# Open-GCI.net
KiCad netlist of a schematic drawn in EAGLE
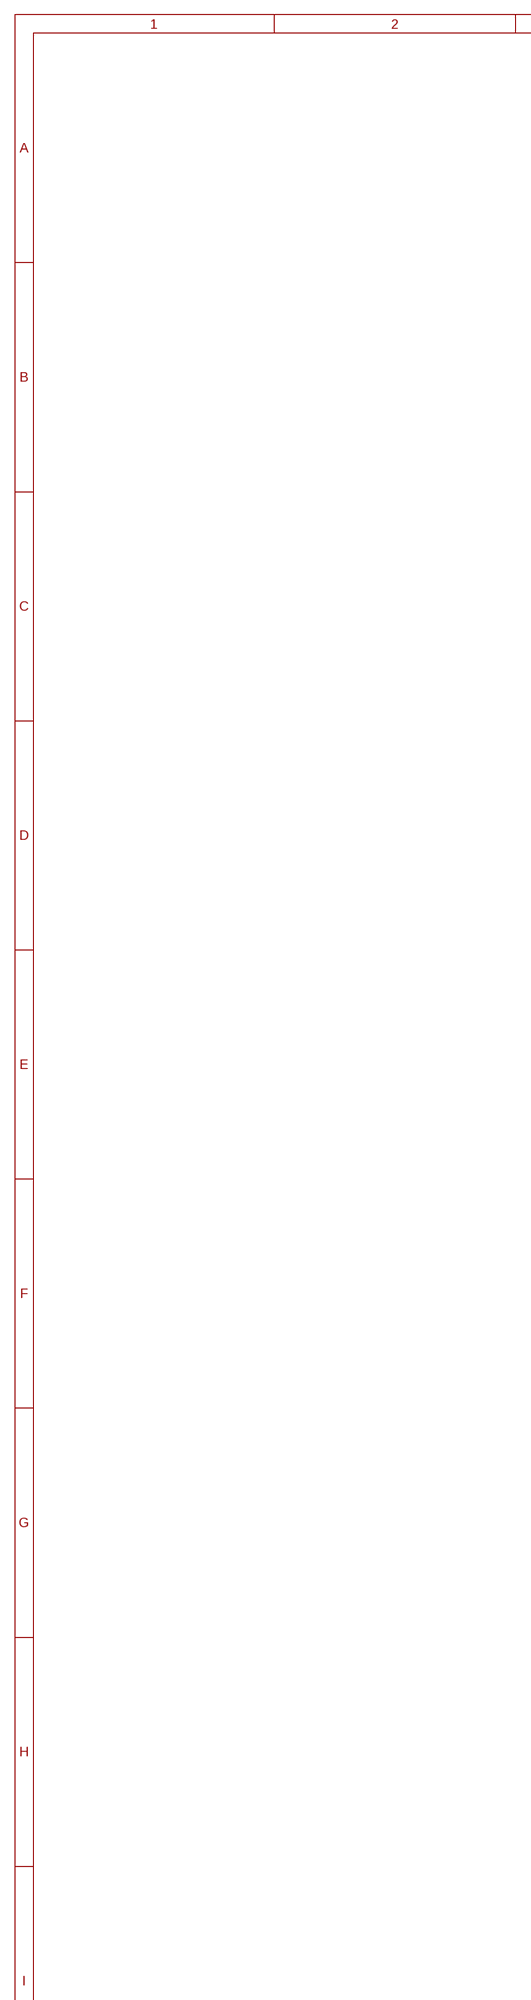
[diagram p0: schematic, sheet 1, part 1 of 2]
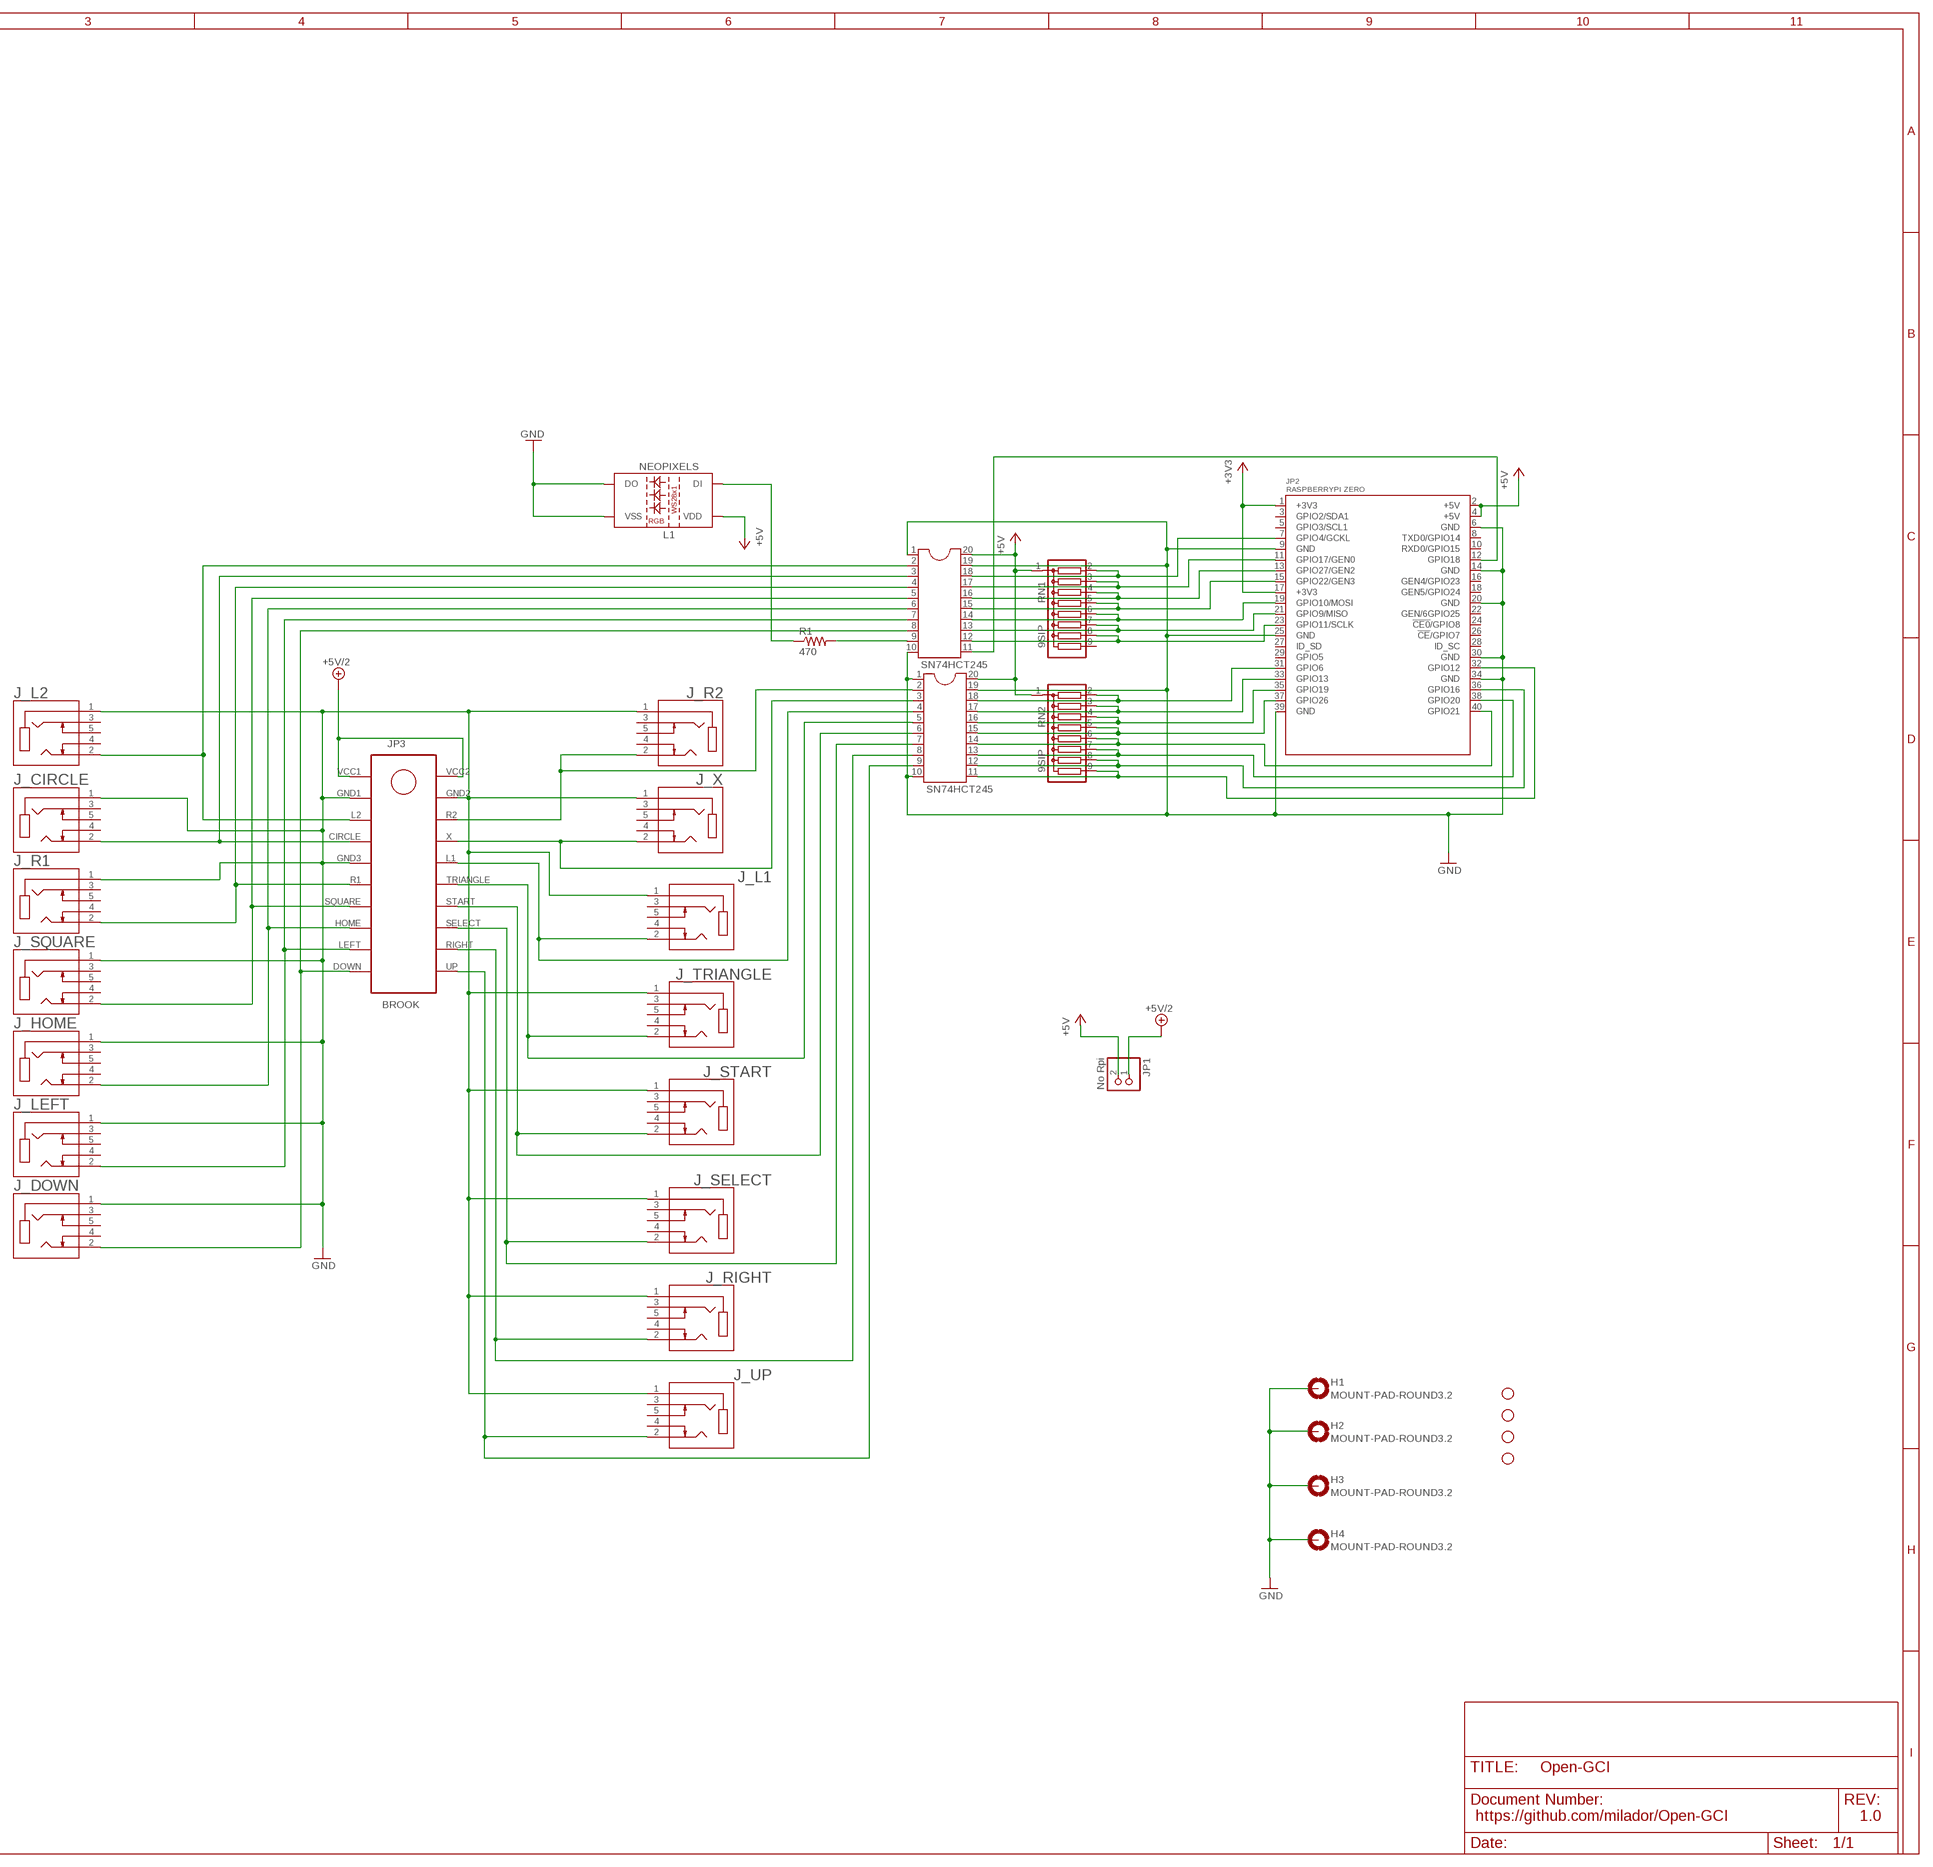
[diagram p1: schematic, sheet 1, part 2 of 2]

(export (version "E")
  (design (tool "Eeschema 10.0.6"))
  (components
    (comp (ref "H1")
      (value "MOUNT-PAD-ROUND3.2")
      (footprint "eagle-import:3,2-PAD")
      (libsource (lib "eagle-import") (part "MOUNT-PAD-ROUND3.2"))
    )
    (comp (ref "H2")
      (value "MOUNT-PAD-ROUND3.2")
      (footprint "eagle-import:3,2-PAD")
      (libsource (lib "eagle-import") (part "MOUNT-PAD-ROUND3.2"))
    )
    (comp (ref "H3")
      (value "MOUNT-PAD-ROUND3.2")
      (footprint "eagle-import:3,2-PAD")
      (libsource (lib "eagle-import") (part "MOUNT-PAD-ROUND3.2"))
    )
    (comp (ref "H4")
      (value "MOUNT-PAD-ROUND3.2")
      (footprint "eagle-import:3,2-PAD")
      (libsource (lib "eagle-import") (part "MOUNT-PAD-ROUND3.2"))
    )
    (comp (ref "H5")
      (value "STAND-OFF")
      (footprint "eagle-import:STAND-OFF")
      (libsource (lib "eagle-import") (part "STAND-OFF"))
    )
    (comp (ref "H6")
      (value "STAND-OFF")
      (footprint "eagle-import:STAND-OFF")
      (libsource (lib "eagle-import") (part "STAND-OFF"))
    )
    (comp (ref "H7")
      (value "STAND-OFF")
      (footprint "eagle-import:STAND-OFF")
      (libsource (lib "eagle-import") (part "STAND-OFF"))
    )
    (comp (ref "H8")
      (value "STAND-OFF")
      (footprint "eagle-import:STAND-OFF")
      (libsource (lib "eagle-import") (part "STAND-OFF"))
    )
    (comp (ref "IC1")
      (value "SN74HCT245")
      (footprint "eagle-import:SN74HCT245")
      (libsource (lib "eagle-import") (part "74HCT245N"))
    )
    (comp (ref "IC2")
      (value "SN74HCT245")
      (footprint "eagle-import:SN74HCT245")
      (libsource (lib "eagle-import") (part "74HCT245N"))
    )
    (comp (ref "JP1")
      (value "No Rpi")
      (footprint "eagle-import:1X02")
      (libsource (lib "eagle-import") (part "PINHD-1X2"))
    )
    (comp (ref "JP2")
      (value "RASPBERRYPI ZERO")
      (footprint "eagle-import:RASPBERRYPI_ZERO")
      (libsource (lib "eagle-import") (part "RASPBERRYPI_ZERO"))
    )
    (comp (ref "JP3")
      (value "BROOK")
      (footprint "eagle-import:CONN_2X10")
      (libsource (lib "eagle-import") (part "BROOK_2X10_FEMALE"))
    )
    (comp (ref "J_CIRCLE")
      (value "SJ1-3535NG")
      (footprint "eagle-import:CUI_SJ1-3535NG")
      (fields (field (name "MANUFACTURER") "CUI"))
      (libsource (lib "eagle-import") (part "SJ1-3535NG"))
    )
    (comp (ref "J_DOWN")
      (value "SJ1-3535NG")
      (footprint "eagle-import:CUI_SJ1-3535NG")
      (fields (field (name "MANUFACTURER") "CUI"))
      (libsource (lib "eagle-import") (part "SJ1-3535NG"))
    )
    (comp (ref "J_HOME")
      (value "SJ1-3535NG")
      (footprint "eagle-import:CUI_SJ1-3535NG")
      (fields (field (name "MANUFACTURER") "CUI"))
      (libsource (lib "eagle-import") (part "SJ1-3535NG"))
    )
    (comp (ref "J_L1")
      (value "SJ1-3535NG")
      (footprint "eagle-import:CUI_SJ1-3535NG")
      (fields (field (name "MANUFACTURER") "CUI"))
      (libsource (lib "eagle-import") (part "SJ1-3535NG"))
    )
    (comp (ref "J_L2")
      (value "SJ1-3535NG")
      (footprint "eagle-import:CUI_SJ1-3535NG")
      (fields (field (name "MANUFACTURER") "CUI"))
      (libsource (lib "eagle-import") (part "SJ1-3535NG"))
    )
    (comp (ref "J_LEFT")
      (value "SJ1-3535NG")
      (footprint "eagle-import:CUI_SJ1-3535NG")
      (fields (field (name "MANUFACTURER") "CUI"))
      (libsource (lib "eagle-import") (part "SJ1-3535NG"))
    )
    (comp (ref "J_R1")
      (value "SJ1-3535NG")
      (footprint "eagle-import:CUI_SJ1-3535NG")
      (fields (field (name "MANUFACTURER") "CUI"))
      (libsource (lib "eagle-import") (part "SJ1-3535NG"))
    )
    (comp (ref "J_R2")
      (value "SJ1-3535NG")
      (footprint "eagle-import:CUI_SJ1-3535NG")
      (fields (field (name "MANUFACTURER") "CUI"))
      (libsource (lib "eagle-import") (part "SJ1-3535NG"))
    )
    (comp (ref "J_RIGHT")
      (value "SJ1-3535NG")
      (footprint "eagle-import:CUI_SJ1-3535NG")
      (fields (field (name "MANUFACTURER") "CUI"))
      (libsource (lib "eagle-import") (part "SJ1-3535NG"))
    )
    (comp (ref "J_SELECT")
      (value "SJ1-3535NG")
      (footprint "eagle-import:CUI_SJ1-3535NG")
      (fields (field (name "MANUFACTURER") "CUI"))
      (libsource (lib "eagle-import") (part "SJ1-3535NG"))
    )
    (comp (ref "J_SQUARE")
      (value "SJ1-3535NG")
      (footprint "eagle-import:CUI_SJ1-3535NG")
      (fields (field (name "MANUFACTURER") "CUI"))
      (libsource (lib "eagle-import") (part "SJ1-3535NG"))
    )
    (comp (ref "J_START")
      (value "SJ1-3535NG")
      (footprint "eagle-import:CUI_SJ1-3535NG")
      (fields (field (name "MANUFACTURER") "CUI"))
      (libsource (lib "eagle-import") (part "SJ1-3535NG"))
    )
    (comp (ref "J_TRIANGLE")
      (value "SJ1-3535NG")
      (footprint "eagle-import:CUI_SJ1-3535NG")
      (fields (field (name "MANUFACTURER") "CUI"))
      (libsource (lib "eagle-import") (part "SJ1-3535NG"))
    )
    (comp (ref "J_UP")
      (value "SJ1-3535NG")
      (footprint "eagle-import:CUI_SJ1-3535NG")
      (fields (field (name "MANUFACTURER") "CUI"))
      (libsource (lib "eagle-import") (part "SJ1-3535NG"))
    )
    (comp (ref "J_X")
      (value "SJ1-3535NG")
      (footprint "eagle-import:CUI_SJ1-3535NG")
      (fields (field (name "MANUFACTURER") "CUI"))
      (libsource (lib "eagle-import") (part "SJ1-3535NG"))
    )
    (comp (ref "L1")
      (value "NEOPIXELS")
      (footprint "eagle-import:NEOPIXELS-5MM")
      (libsource (lib "eagle-import") (part "NEOPIXELS-5MM"))
    )
    (comp (ref "R1")
      (value "470")
      (footprint "eagle-import:0204_7")
      (libsource (lib "eagle-import") (part "R-US_0204/7"))
    )
    (comp (ref "RN1")
      (value "9SIP")
      (footprint "eagle-import:SIL9")
      (libsource (lib "eagle-import") (part "SIL9"))
    )
    (comp (ref "RN2")
      (value "9SIP")
      (footprint "eagle-import:SIL9")
      (libsource (lib "eagle-import") (part "SIL9"))
    )
  )
  (nets
    (net (code "1") (name "+3V3") (class "Default")
      (node (ref "JP2") (pin "1") (pinfunction "+3V3_1") (pintype "power_in"))
      (node (ref "JP2") (pin "17") (pinfunction "+3V3_17") (pintype "power_in"))
    )
    (net (code "2") (name "+5V") (class "Default")
      (node (ref "IC1") (pin "20") (pinfunction "20_20") (pintype "passive"))
      (node (ref "IC2") (pin "20") (pinfunction "20_20") (pintype "passive"))
      (node (ref "JP1") (pin "2") (pinfunction "2_2") (pintype "passive"))
      (node (ref "JP2") (pin "2") (pinfunction "+5V_2") (pintype "power_in"))
      (node (ref "JP2") (pin "4") (pinfunction "+5V_4") (pintype "power_in"))
      (node (ref "L1") (pin "2") (pinfunction "VDD_2") (pintype "bidirectional"))
      (node (ref "RN1") (pin "1") (pinfunction "1_1") (pintype "passive"))
      (node (ref "RN2") (pin "1") (pinfunction "1_1") (pintype "passive"))
    )
    (net (code "3") (name "+5V{slash}2") (class "Default")
      (node (ref "JP1") (pin "1") (pinfunction "1_1") (pintype "passive"))
      (node (ref "JP3") (pin "VCC1") (pinfunction "VCC1_VCC1") (pintype "passive"))
      (node (ref "JP3") (pin "VCC2") (pinfunction "VCC2_VCC2") (pintype "passive"))
    )
    (net (code "4") (name "GND") (class "Default")
      (node (ref "H1") (pin "B3,2") (pinfunction "MOUNT_B3,2") (pintype "passive"))
      (node (ref "H2") (pin "B3,2") (pinfunction "MOUNT_B3,2") (pintype "passive"))
      (node (ref "H3") (pin "B3,2") (pinfunction "MOUNT_B3,2") (pintype "passive"))
      (node (ref "H4") (pin "B3,2") (pinfunction "MOUNT_B3,2") (pintype "passive"))
      (node (ref "IC1") (pin "1") (pinfunction "1_1") (pintype "passive"))
      (node (ref "IC1") (pin "10") (pinfunction "10_10") (pintype "passive"))
      (node (ref "IC1") (pin "19") (pinfunction "19_19") (pintype "passive"))
      (node (ref "IC2") (pin "1") (pinfunction "1_1") (pintype "passive"))
      (node (ref "IC2") (pin "10") (pinfunction "10_10") (pintype "passive"))
      (node (ref "IC2") (pin "19") (pinfunction "19_19") (pintype "passive"))
      (node (ref "JP2") (pin "14") (pinfunction "GND_14") (pintype "power_in"))
      (node (ref "JP2") (pin "20") (pinfunction "GND_20") (pintype "power_in"))
      (node (ref "JP2") (pin "25") (pinfunction "GND_25") (pintype "power_in"))
      (node (ref "JP2") (pin "30") (pinfunction "GND_30") (pintype "power_in"))
      (node (ref "JP2") (pin "34") (pinfunction "GND_34") (pintype "power_in"))
      (node (ref "JP2") (pin "39") (pinfunction "GND_39") (pintype "power_in"))
      (node (ref "JP2") (pin "6") (pinfunction "GND_6") (pintype "power_in"))
      (node (ref "JP2") (pin "9") (pinfunction "GND_9") (pintype "power_in"))
      (node (ref "JP3") (pin "GND1") (pinfunction "GND1_GND1") (pintype "passive"))
      (node (ref "JP3") (pin "GND2") (pinfunction "GND2_GND2") (pintype "passive"))
      (node (ref "JP3") (pin "GND3") (pinfunction "GND3_GND3") (pintype "passive"))
      (node (ref "J_CIRCLE") (pin "1") (pinfunction "1_1") (pintype "passive"))
      (node (ref "J_DOWN") (pin "1") (pinfunction "1_1") (pintype "passive"))
      (node (ref "J_HOME") (pin "1") (pinfunction "1_1") (pintype "passive"))
      (node (ref "J_L1") (pin "1") (pinfunction "1_1") (pintype "passive"))
      (node (ref "J_L2") (pin "1") (pinfunction "1_1") (pintype "passive"))
      (node (ref "J_LEFT") (pin "1") (pinfunction "1_1") (pintype "passive"))
      (node (ref "J_R1") (pin "1") (pinfunction "1_1") (pintype "passive"))
      (node (ref "J_R2") (pin "1") (pinfunction "1_1") (pintype "passive"))
      (node (ref "J_RIGHT") (pin "1") (pinfunction "1_1") (pintype "passive"))
      (node (ref "J_SELECT") (pin "1") (pinfunction "1_1") (pintype "passive"))
      (node (ref "J_SQUARE") (pin "1") (pinfunction "1_1") (pintype "passive"))
      (node (ref "J_START") (pin "1") (pinfunction "1_1") (pintype "passive"))
      (node (ref "J_TRIANGLE") (pin "1") (pinfunction "1_1") (pintype "passive"))
      (node (ref "J_UP") (pin "1") (pinfunction "1_1") (pintype "passive"))
      (node (ref "J_X") (pin "1") (pinfunction "1_1") (pintype "passive"))
      (node (ref "L1") (pin "3") (pinfunction "VSS_3") (pintype "bidirectional"))
      (node (ref "L1") (pin "4") (pinfunction "DO_4") (pintype "bidirectional"))
    )
    (net (code "5") (name "Net-(IC1-Pad2)") (class "Default")
      (node (ref "IC1") (pin "2") (pinfunction "2_2") (pintype "passive"))
      (node (ref "JP3") (pin "L2") (pinfunction "L2_L2") (pintype "passive"))
      (node (ref "J_L2") (pin "2") (pinfunction "2_2") (pintype "passive"))
    )
    (net (code "6") (name "Net-(IC1-Pad3)") (class "Default")
      (node (ref "IC1") (pin "3") (pinfunction "3_3") (pintype "passive"))
      (node (ref "JP3") (pin "CIRCLE") (pinfunction "CIRCLE_CIRCLE") (pintype "passive"))
      (node (ref "J_CIRCLE") (pin "2") (pinfunction "2_2") (pintype "passive"))
    )
    (net (code "7") (name "Net-(IC1-Pad4)") (class "Default")
      (node (ref "IC1") (pin "4") (pinfunction "4_4") (pintype "passive"))
      (node (ref "JP3") (pin "R1") (pinfunction "R1_R1") (pintype "passive"))
      (node (ref "J_R1") (pin "2") (pinfunction "2_2") (pintype "passive"))
    )
    (net (code "8") (name "Net-(IC1-Pad5)") (class "Default")
      (node (ref "IC1") (pin "5") (pinfunction "5_5") (pintype "passive"))
      (node (ref "JP3") (pin "SQUARE") (pinfunction "SQUARE_SQUARE") (pintype "passive"))
      (node (ref "J_SQUARE") (pin "2") (pinfunction "2_2") (pintype "passive"))
    )
    (net (code "9") (name "Net-(IC1-Pad6)") (class "Default")
      (node (ref "IC1") (pin "6") (pinfunction "6_6") (pintype "passive"))
      (node (ref "JP3") (pin "HOME") (pinfunction "HOME_HOME") (pintype "passive"))
      (node (ref "J_HOME") (pin "2") (pinfunction "2_2") (pintype "passive"))
    )
    (net (code "10") (name "Net-(IC1-Pad7)") (class "Default")
      (node (ref "IC1") (pin "7") (pinfunction "7_7") (pintype "passive"))
      (node (ref "JP3") (pin "LEFT") (pinfunction "LEFT_LEFT") (pintype "passive"))
      (node (ref "J_LEFT") (pin "2") (pinfunction "2_2") (pintype "passive"))
    )
    (net (code "11") (name "Net-(IC1-Pad8)") (class "Default")
      (node (ref "IC1") (pin "8") (pinfunction "8_8") (pintype "passive"))
      (node (ref "JP3") (pin "DOWN") (pinfunction "DOWN_DOWN") (pintype "passive"))
      (node (ref "J_DOWN") (pin "2") (pinfunction "2_2") (pintype "passive"))
    )
    (net (code "12") (name "Net-(IC1-Pad9)") (class "Default")
      (node (ref "IC1") (pin "9") (pinfunction "9_9") (pintype "passive"))
      (node (ref "R1") (pin "2") (pinfunction "2_2") (pintype "passive"))
    )
    (net (code "13") (name "Net-(IC2-Pad2)") (class "Default")
      (node (ref "IC2") (pin "2") (pinfunction "2_2") (pintype "passive"))
      (node (ref "JP3") (pin "R2") (pinfunction "R2_R2") (pintype "passive"))
      (node (ref "J_R2") (pin "2") (pinfunction "2_2") (pintype "passive"))
    )
    (net (code "14") (name "Net-(IC2-Pad3)") (class "Default")
      (node (ref "IC2") (pin "3") (pinfunction "3_3") (pintype "passive"))
      (node (ref "JP3") (pin "X") (pinfunction "X_X") (pintype "passive"))
      (node (ref "J_X") (pin "2") (pinfunction "2_2") (pintype "passive"))
    )
    (net (code "15") (name "Net-(IC2-Pad4)") (class "Default")
      (node (ref "IC2") (pin "4") (pinfunction "4_4") (pintype "passive"))
      (node (ref "JP3") (pin "L1") (pinfunction "L1_L1") (pintype "passive"))
      (node (ref "J_L1") (pin "2") (pinfunction "2_2") (pintype "passive"))
    )
    (net (code "16") (name "Net-(IC2-Pad5)") (class "Default")
      (node (ref "IC2") (pin "5") (pinfunction "5_5") (pintype "passive"))
      (node (ref "JP3") (pin "TRIANGLE") (pinfunction "TRIANGLE_TRIANGLE") (pintype "passive"))
      (node (ref "J_TRIANGLE") (pin "2") (pinfunction "2_2") (pintype "passive"))
    )
    (net (code "17") (name "Net-(IC2-Pad6)") (class "Default")
      (node (ref "IC2") (pin "6") (pinfunction "6_6") (pintype "passive"))
      (node (ref "JP3") (pin "START") (pinfunction "START_START") (pintype "passive"))
      (node (ref "J_START") (pin "2") (pinfunction "2_2") (pintype "passive"))
    )
    (net (code "18") (name "Net-(IC2-Pad7)") (class "Default")
      (node (ref "IC2") (pin "7") (pinfunction "7_7") (pintype "passive"))
      (node (ref "JP3") (pin "SELECT") (pinfunction "SELECT_SELECT") (pintype "passive"))
      (node (ref "J_SELECT") (pin "2") (pinfunction "2_2") (pintype "passive"))
    )
    (net (code "19") (name "Net-(IC2-Pad8)") (class "Default")
      (node (ref "IC2") (pin "8") (pinfunction "8_8") (pintype "passive"))
      (node (ref "JP3") (pin "RIGHT") (pinfunction "RIGHT_RIGHT") (pintype "passive"))
      (node (ref "J_RIGHT") (pin "2") (pinfunction "2_2") (pintype "passive"))
    )
    (net (code "20") (name "Net-(IC2-Pad9)") (class "Default")
      (node (ref "IC2") (pin "9") (pinfunction "9_9") (pintype "passive"))
      (node (ref "JP3") (pin "UP") (pinfunction "UP_UP") (pintype "passive"))
      (node (ref "J_UP") (pin "2") (pinfunction "2_2") (pintype "passive"))
    )
    (net (code "21") (name "Net-(JP2-GPIO4{slash}GCKL)") (class "Default")
      (node (ref "IC1") (pin "18") (pinfunction "18_18") (pintype "passive"))
      (node (ref "JP2") (pin "7") (pinfunction "GPIO4/GCKL_7") (pintype "bidirectional"))
      (node (ref "RN1") (pin "2") (pinfunction "2_2") (pintype "passive"))
    )
    (net (code "22") (name "Net-(JP2-GPIO6)") (class "Default")
      (node (ref "IC2") (pin "18") (pinfunction "18_18") (pintype "passive"))
      (node (ref "JP2") (pin "31") (pinfunction "GPIO6_31") (pintype "bidirectional"))
      (node (ref "RN2") (pin "2") (pinfunction "2_2") (pintype "passive"))
    )
    (net (code "23") (name "Net-(JP2-GPIO9{slash}MISO)") (class "Default")
      (node (ref "IC1") (pin "13") (pinfunction "13_13") (pintype "passive"))
      (node (ref "JP2") (pin "21") (pinfunction "GPIO9/MISO_21") (pintype "bidirectional"))
      (node (ref "RN1") (pin "7") (pinfunction "7_7") (pintype "passive"))
    )
    (net (code "24") (name "Net-(JP2-GPIO10{slash}MOSI)") (class "Default")
      (node (ref "IC1") (pin "14") (pinfunction "14_14") (pintype "passive"))
      (node (ref "JP2") (pin "19") (pinfunction "GPIO10/MOSI_19") (pintype "bidirectional"))
      (node (ref "RN1") (pin "6") (pinfunction "6_6") (pintype "passive"))
    )
    (net (code "25") (name "Net-(JP2-GPIO11{slash}SCLK)") (class "Default")
      (node (ref "IC1") (pin "12") (pinfunction "12_12") (pintype "passive"))
      (node (ref "JP2") (pin "23") (pinfunction "GPIO11/SCLK_23") (pintype "bidirectional"))
      (node (ref "RN1") (pin "8") (pinfunction "8_8") (pintype "passive"))
    )
    (net (code "26") (name "Net-(JP2-GPIO12)") (class "Default")
      (node (ref "IC2") (pin "11") (pinfunction "11_11") (pintype "passive"))
      (node (ref "JP2") (pin "32") (pinfunction "GPIO12_32") (pintype "bidirectional"))
      (node (ref "RN2") (pin "9") (pinfunction "9_9") (pintype "passive"))
    )
    (net (code "27") (name "Net-(JP2-GPIO13)") (class "Default")
      (node (ref "IC2") (pin "17") (pinfunction "17_17") (pintype "passive"))
      (node (ref "JP2") (pin "33") (pinfunction "GPIO13_33") (pintype "bidirectional"))
      (node (ref "RN2") (pin "3") (pinfunction "3_3") (pintype "passive"))
    )
    (net (code "28") (name "Net-(JP2-GPIO16)") (class "Default")
      (node (ref "IC2") (pin "12") (pinfunction "12_12") (pintype "passive"))
      (node (ref "JP2") (pin "36") (pinfunction "GPIO16_36") (pintype "bidirectional"))
      (node (ref "RN2") (pin "8") (pinfunction "8_8") (pintype "passive"))
    )
    (net (code "29") (name "Net-(JP2-GPIO17{slash}GEN0)") (class "Default")
      (node (ref "IC1") (pin "17") (pinfunction "17_17") (pintype "passive"))
      (node (ref "JP2") (pin "11") (pinfunction "GPIO17/GEN0_11") (pintype "bidirectional"))
      (node (ref "RN1") (pin "3") (pinfunction "3_3") (pintype "passive"))
    )
    (net (code "30") (name "Net-(JP2-GPIO18)") (class "Default")
      (node (ref "IC1") (pin "11") (pinfunction "11_11") (pintype "passive"))
      (node (ref "JP2") (pin "12") (pinfunction "GPIO18_12") (pintype "bidirectional"))
    )
    (net (code "31") (name "Net-(JP2-GPIO19)") (class "Default")
      (node (ref "IC2") (pin "16") (pinfunction "16_16") (pintype "passive"))
      (node (ref "JP2") (pin "35") (pinfunction "GPIO19_35") (pintype "bidirectional"))
      (node (ref "RN2") (pin "4") (pinfunction "4_4") (pintype "passive"))
    )
    (net (code "32") (name "Net-(JP2-GPIO20)") (class "Default")
      (node (ref "IC2") (pin "13") (pinfunction "13_13") (pintype "passive"))
      (node (ref "JP2") (pin "38") (pinfunction "GPIO20_38") (pintype "bidirectional"))
      (node (ref "RN2") (pin "7") (pinfunction "7_7") (pintype "passive"))
    )
    (net (code "33") (name "Net-(JP2-GPIO21)") (class "Default")
      (node (ref "IC2") (pin "14") (pinfunction "14_14") (pintype "passive"))
      (node (ref "JP2") (pin "40") (pinfunction "GPIO21_40") (pintype "bidirectional"))
      (node (ref "RN2") (pin "6") (pinfunction "6_6") (pintype "passive"))
    )
    (net (code "34") (name "Net-(JP2-GPIO22{slash}GEN3)") (class "Default")
      (node (ref "IC1") (pin "15") (pinfunction "15_15") (pintype "passive"))
      (node (ref "JP2") (pin "15") (pinfunction "GPIO22/GEN3_15") (pintype "bidirectional"))
      (node (ref "RN1") (pin "5") (pinfunction "5_5") (pintype "passive"))
    )
    (net (code "35") (name "Net-(JP2-GPIO26)") (class "Default")
      (node (ref "IC2") (pin "15") (pinfunction "15_15") (pintype "passive"))
      (node (ref "JP2") (pin "37") (pinfunction "GPIO26_37") (pintype "bidirectional"))
      (node (ref "RN2") (pin "5") (pinfunction "5_5") (pintype "passive"))
    )
    (net (code "36") (name "Net-(JP2-GPIO27{slash}GEN2)") (class "Default")
      (node (ref "IC1") (pin "16") (pinfunction "16_16") (pintype "passive"))
      (node (ref "JP2") (pin "13") (pinfunction "GPIO27/GEN2_13") (pintype "bidirectional"))
      (node (ref "RN1") (pin "4") (pinfunction "4_4") (pintype "passive"))
    )
    (net (code "37") (name "Net-(L1-DI)") (class "Default")
      (node (ref "L1") (pin "1") (pinfunction "DI_1") (pintype "bidirectional"))
      (node (ref "R1") (pin "1") (pinfunction "1_1") (pintype "passive"))
    )
    (net (code "38") (name "unconnected-(JP2-GEN4{slash}GPIO23-Pad16)") (class "Default")
      (node (ref "JP2") (pin "16") (pinfunction "GEN4/GPIO23_16") (pintype "bidirectional"))
    )
    (net (code "39") (name "unconnected-(JP2-GEN5{slash}GPIO24-Pad18)") (class "Default")
      (node (ref "JP2") (pin "18") (pinfunction "GEN5/GPIO24_18") (pintype "bidirectional"))
    )
    (net (code "40") (name "unconnected-(JP2-GEN{slash}6GPIO25-Pad22)") (class "Default")
      (node (ref "JP2") (pin "22") (pinfunction "GEN/6GPIO25_22") (pintype "bidirectional"))
    )
    (net (code "41") (name "unconnected-(JP2-GPIO2{slash}SDA1-Pad3)") (class "Default")
      (node (ref "JP2") (pin "3") (pinfunction "GPIO2/SDA1_3") (pintype "bidirectional"))
    )
    (net (code "42") (name "unconnected-(JP2-GPIO3{slash}SCL1-Pad5)") (class "Default")
      (node (ref "JP2") (pin "5") (pinfunction "GPIO3/SCL1_5") (pintype "bidirectional"))
    )
    (net (code "43") (name "unconnected-(JP2-GPIO5-Pad29)") (class "Default")
      (node (ref "JP2") (pin "29") (pinfunction "GPIO5_29") (pintype "bidirectional"))
    )
    (net (code "44") (name "unconnected-(JP2-ID_SC-Pad28)") (class "Default")
      (node (ref "JP2") (pin "28") (pinfunction "ID_SC_28") (pintype "bidirectional"))
    )
    (net (code "45") (name "unconnected-(JP2-ID_SD-Pad27)") (class "Default")
      (node (ref "JP2") (pin "27") (pinfunction "ID_SD_27") (pintype "bidirectional"))
    )
    (net (code "46") (name "unconnected-(JP2-RXD0{slash}GPIO15-Pad10)") (class "Default")
      (node (ref "JP2") (pin "10") (pinfunction "RXD0/GPIO15_10") (pintype "bidirectional"))
    )
    (net (code "47") (name "unconnected-(JP2-TXD0{slash}GPIO14-Pad8)") (class "Default")
      (node (ref "JP2") (pin "8") (pinfunction "TXD0/GPIO14_8") (pintype "bidirectional"))
    )
    (net (code "48") (name "unconnected-(JP2-~{CE0}{slash}GPIO8-Pad24)") (class "Default")
      (node (ref "JP2") (pin "24") (pinfunction "~{CE0}/GPIO8_24") (pintype "bidirectional"))
    )
    (net (code "49") (name "unconnected-(JP2-~{CE}{slash}GPIO7-Pad26)") (class "Default")
      (node (ref "JP2") (pin "26") (pinfunction "~{CE}/GPIO7_26") (pintype "bidirectional"))
    )
    (net (code "50") (name "unconnected-(J_CIRCLE-Pad3)") (class "Default")
      (node (ref "J_CIRCLE") (pin "3") (pinfunction "3_3") (pintype "passive"))
    )
    (net (code "51") (name "unconnected-(J_CIRCLE-Pad4)") (class "Default")
      (node (ref "J_CIRCLE") (pin "4") (pinfunction "4_4") (pintype "passive"))
    )
    (net (code "52") (name "unconnected-(J_CIRCLE-Pad5)") (class "Default")
      (node (ref "J_CIRCLE") (pin "5") (pinfunction "5_5") (pintype "passive"))
    )
    (net (code "53") (name "unconnected-(J_DOWN-Pad3)") (class "Default")
      (node (ref "J_DOWN") (pin "3") (pinfunction "3_3") (pintype "passive"))
    )
    (net (code "54") (name "unconnected-(J_DOWN-Pad4)") (class "Default")
      (node (ref "J_DOWN") (pin "4") (pinfunction "4_4") (pintype "passive"))
    )
    (net (code "55") (name "unconnected-(J_DOWN-Pad5)") (class "Default")
      (node (ref "J_DOWN") (pin "5") (pinfunction "5_5") (pintype "passive"))
    )
    (net (code "56") (name "unconnected-(J_HOME-Pad3)") (class "Default")
      (node (ref "J_HOME") (pin "3") (pinfunction "3_3") (pintype "passive"))
    )
    (net (code "57") (name "unconnected-(J_HOME-Pad4)") (class "Default")
      (node (ref "J_HOME") (pin "4") (pinfunction "4_4") (pintype "passive"))
    )
    (net (code "58") (name "unconnected-(J_HOME-Pad5)") (class "Default")
      (node (ref "J_HOME") (pin "5") (pinfunction "5_5") (pintype "passive"))
    )
    (net (code "59") (name "unconnected-(J_L1-Pad3)") (class "Default")
      (node (ref "J_L1") (pin "3") (pinfunction "3_3") (pintype "passive"))
    )
    (net (code "60") (name "unconnected-(J_L1-Pad4)") (class "Default")
      (node (ref "J_L1") (pin "4") (pinfunction "4_4") (pintype "passive"))
    )
    (net (code "61") (name "unconnected-(J_L1-Pad5)") (class "Default")
      (node (ref "J_L1") (pin "5") (pinfunction "5_5") (pintype "passive"))
    )
    (net (code "62") (name "unconnected-(J_L2-Pad3)") (class "Default")
      (node (ref "J_L2") (pin "3") (pinfunction "3_3") (pintype "passive"))
    )
    (net (code "63") (name "unconnected-(J_L2-Pad4)") (class "Default")
      (node (ref "J_L2") (pin "4") (pinfunction "4_4") (pintype "passive"))
    )
    (net (code "64") (name "unconnected-(J_L2-Pad5)") (class "Default")
      (node (ref "J_L2") (pin "5") (pinfunction "5_5") (pintype "passive"))
    )
    (net (code "65") (name "unconnected-(J_LEFT-Pad3)") (class "Default")
      (node (ref "J_LEFT") (pin "3") (pinfunction "3_3") (pintype "passive"))
    )
    (net (code "66") (name "unconnected-(J_LEFT-Pad4)") (class "Default")
      (node (ref "J_LEFT") (pin "4") (pinfunction "4_4") (pintype "passive"))
    )
    (net (code "67") (name "unconnected-(J_LEFT-Pad5)") (class "Default")
      (node (ref "J_LEFT") (pin "5") (pinfunction "5_5") (pintype "passive"))
    )
    (net (code "68") (name "unconnected-(J_R1-Pad3)") (class "Default")
      (node (ref "J_R1") (pin "3") (pinfunction "3_3") (pintype "passive"))
    )
    (net (code "69") (name "unconnected-(J_R1-Pad4)") (class "Default")
      (node (ref "J_R1") (pin "4") (pinfunction "4_4") (pintype "passive"))
    )
    (net (code "70") (name "unconnected-(J_R1-Pad5)") (class "Default")
      (node (ref "J_R1") (pin "5") (pinfunction "5_5") (pintype "passive"))
    )
    (net (code "71") (name "unconnected-(J_R2-Pad3)") (class "Default")
      (node (ref "J_R2") (pin "3") (pinfunction "3_3") (pintype "passive"))
    )
    (net (code "72") (name "unconnected-(J_R2-Pad4)") (class "Default")
      (node (ref "J_R2") (pin "4") (pinfunction "4_4") (pintype "passive"))
    )
    (net (code "73") (name "unconnected-(J_R2-Pad5)") (class "Default")
      (node (ref "J_R2") (pin "5") (pinfunction "5_5") (pintype "passive"))
    )
    (net (code "74") (name "unconnected-(J_RIGHT-Pad3)") (class "Default")
      (node (ref "J_RIGHT") (pin "3") (pinfunction "3_3") (pintype "passive"))
    )
    (net (code "75") (name "unconnected-(J_RIGHT-Pad4)") (class "Default")
      (node (ref "J_RIGHT") (pin "4") (pinfunction "4_4") (pintype "passive"))
    )
    (net (code "76") (name "unconnected-(J_RIGHT-Pad5)") (class "Default")
      (node (ref "J_RIGHT") (pin "5") (pinfunction "5_5") (pintype "passive"))
    )
    (net (code "77") (name "unconnected-(J_SELECT-Pad3)") (class "Default")
      (node (ref "J_SELECT") (pin "3") (pinfunction "3_3") (pintype "passive"))
    )
    (net (code "78") (name "unconnected-(J_SELECT-Pad4)") (class "Default")
      (node (ref "J_SELECT") (pin "4") (pinfunction "4_4") (pintype "passive"))
    )
    (net (code "79") (name "unconnected-(J_SELECT-Pad5)") (class "Default")
      (node (ref "J_SELECT") (pin "5") (pinfunction "5_5") (pintype "passive"))
    )
    (net (code "80") (name "unconnected-(J_SQUARE-Pad3)") (class "Default")
      (node (ref "J_SQUARE") (pin "3") (pinfunction "3_3") (pintype "passive"))
    )
    (net (code "81") (name "unconnected-(J_SQUARE-Pad4)") (class "Default")
      (node (ref "J_SQUARE") (pin "4") (pinfunction "4_4") (pintype "passive"))
    )
    (net (code "82") (name "unconnected-(J_SQUARE-Pad5)") (class "Default")
      (node (ref "J_SQUARE") (pin "5") (pinfunction "5_5") (pintype "passive"))
    )
    (net (code "83") (name "unconnected-(J_START-Pad3)") (class "Default")
      (node (ref "J_START") (pin "3") (pinfunction "3_3") (pintype "passive"))
    )
    (net (code "84") (name "unconnected-(J_START-Pad4)") (class "Default")
      (node (ref "J_START") (pin "4") (pinfunction "4_4") (pintype "passive"))
    )
    (net (code "85") (name "unconnected-(J_START-Pad5)") (class "Default")
      (node (ref "J_START") (pin "5") (pinfunction "5_5") (pintype "passive"))
    )
    (net (code "86") (name "unconnected-(J_TRIANGLE-Pad3)") (class "Default")
      (node (ref "J_TRIANGLE") (pin "3") (pinfunction "3_3") (pintype "passive"))
    )
    (net (code "87") (name "unconnected-(J_TRIANGLE-Pad4)") (class "Default")
      (node (ref "J_TRIANGLE") (pin "4") (pinfunction "4_4") (pintype "passive"))
    )
    (net (code "88") (name "unconnected-(J_TRIANGLE-Pad5)") (class "Default")
      (node (ref "J_TRIANGLE") (pin "5") (pinfunction "5_5") (pintype "passive"))
    )
    (net (code "89") (name "unconnected-(J_UP-Pad3)") (class "Default")
      (node (ref "J_UP") (pin "3") (pinfunction "3_3") (pintype "passive"))
    )
    (net (code "90") (name "unconnected-(J_UP-Pad4)") (class "Default")
      (node (ref "J_UP") (pin "4") (pinfunction "4_4") (pintype "passive"))
    )
    (net (code "91") (name "unconnected-(J_UP-Pad5)") (class "Default")
      (node (ref "J_UP") (pin "5") (pinfunction "5_5") (pintype "passive"))
    )
    (net (code "92") (name "unconnected-(J_X-Pad3)") (class "Default")
      (node (ref "J_X") (pin "3") (pinfunction "3_3") (pintype "passive"))
    )
    (net (code "93") (name "unconnected-(J_X-Pad4)") (class "Default")
      (node (ref "J_X") (pin "4") (pinfunction "4_4") (pintype "passive"))
    )
    (net (code "94") (name "unconnected-(J_X-Pad5)") (class "Default")
      (node (ref "J_X") (pin "5") (pinfunction "5_5") (pintype "passive"))
    )
    (net (code "95") (name "unconnected-(RN1-Pad9)") (class "Default")
      (node (ref "RN1") (pin "9") (pinfunction "9_9") (pintype "passive"))
    )
  )
)
